# sense.net
KiCad netlist of a schematic drawn in EAGLE
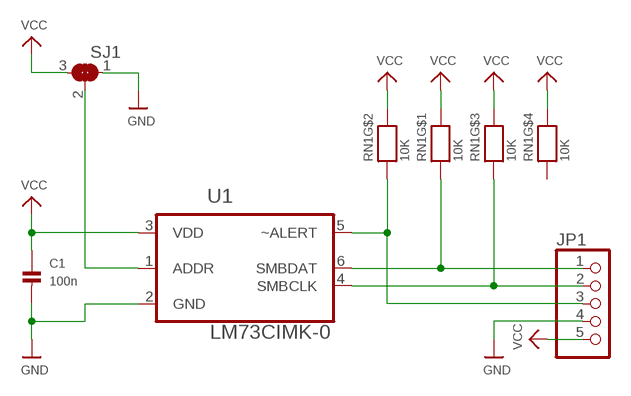
[diagram p0: schematic, sheet 1]

(export (version "E")
  (design (tool "Eeschema 10.0.6"))
  (components
    (comp (ref "C1")
      (value "100n")
      (footprint "eagle-import:0805")
      (libsource (lib "eagle-import") (part "CAP_CERAMIC0805"))
    )
    (comp (ref "JP1")
      (value "PINHD-1X5")
      (footprint "eagle-import:1X05")
      (libsource (lib "eagle-import") (part "PINHD-1X5"))
    )
    (comp (ref "RN1")
      (value "10K")
      (footprint "eagle-import:RESPACK_4X0603")
      (libsource (lib "eagle-import") (part "RESISTOR_4PACK"))
    )
    (comp (ref "SJ1")
      (value "SOLDERJUMPER_2WAY0603")
      (footprint "eagle-import:SOLDERJUMPER_2WAY_OPEN_0603")
      (libsource (lib "eagle-import") (part "SOLDERJUMPER_2WAY0603"))
    )
    (comp (ref "U1")
      (value "LM73CIMK-0")
      (footprint "eagle-import:SOT95P285X100-6N")
      (libsource (lib "eagle-import") (part "LM73CIMK-0"))
    )
  )
  (nets
    (net (code "1") (name "GND") (class "Default")
      (node (ref "C1") (pin "2") (pinfunction "P$2_2") (pintype "passive"))
      (node (ref "JP1") (pin "4") (pinfunction "4_4") (pintype "passive"))
      (node (ref "SJ1") (pin "1") (pinfunction "1_1") (pintype "passive"))
      (node (ref "U1") (pin "2") (pinfunction "GND_2") (pintype "passive"))
    )
    (net (code "2") (name "Net-(RN1B-1)") (class "Default")
      (node (ref "JP1") (pin "3") (pinfunction "3_3") (pintype "passive"))
      (node (ref "RN1") (pin "2") (pinfunction "1_2") (pintype "passive"))
      (node (ref "U1") (pin "5") (pinfunction "~{ALERT}_5") (pintype "output"))
    )
    (net (code "3") (name "Net-(RN1C-1)") (class "Default")
      (node (ref "JP1") (pin "2") (pinfunction "2_2") (pintype "passive"))
      (node (ref "RN1") (pin "3") (pinfunction "1_3") (pintype "passive"))
      (node (ref "U1") (pin "4") (pinfunction "SMBCLK_4") (pintype "input"))
    )
    (net (code "4") (name "Net-(U1-ADDR)") (class "Default")
      (node (ref "SJ1") (pin "2") (pinfunction "2_2") (pintype "passive"))
      (node (ref "U1") (pin "1") (pinfunction "ADDR_1") (pintype "input"))
    )
    (net (code "5") (name "Net-(U1-SMBDAT)") (class "Default")
      (node (ref "JP1") (pin "1") (pinfunction "1_1") (pintype "passive"))
      (node (ref "RN1") (pin "1") (pinfunction "1_1") (pintype "passive"))
      (node (ref "U1") (pin "6") (pinfunction "SMBDAT_6") (pintype "bidirectional"))
    )
    (net (code "6") (name "VCC") (class "Default")
      (node (ref "C1") (pin "1") (pinfunction "P$1_1") (pintype "passive"))
      (node (ref "JP1") (pin "5") (pinfunction "5_5") (pintype "passive"))
      (node (ref "RN1") (pin "5") (pinfunction "2_5") (pintype "passive"))
      (node (ref "RN1") (pin "6") (pinfunction "2_6") (pintype "passive"))
      (node (ref "RN1") (pin "7") (pinfunction "2_7") (pintype "passive"))
      (node (ref "RN1") (pin "8") (pinfunction "2_8") (pintype "passive"))
      (node (ref "SJ1") (pin "3") (pinfunction "3_3") (pintype "passive"))
      (node (ref "U1") (pin "3") (pinfunction "VDD_3") (pintype "power_in"))
    )
    (net (code "7") (name "unconnected-(RN1D-1-Pad4)") (class "Default")
      (node (ref "RN1") (pin "4") (pinfunction "1_4") (pintype "passive"))
    )
  )
)
